# SMC_ISO_Interface_V2_0.net
KiCad netlist of a schematic drawn in EAGLE
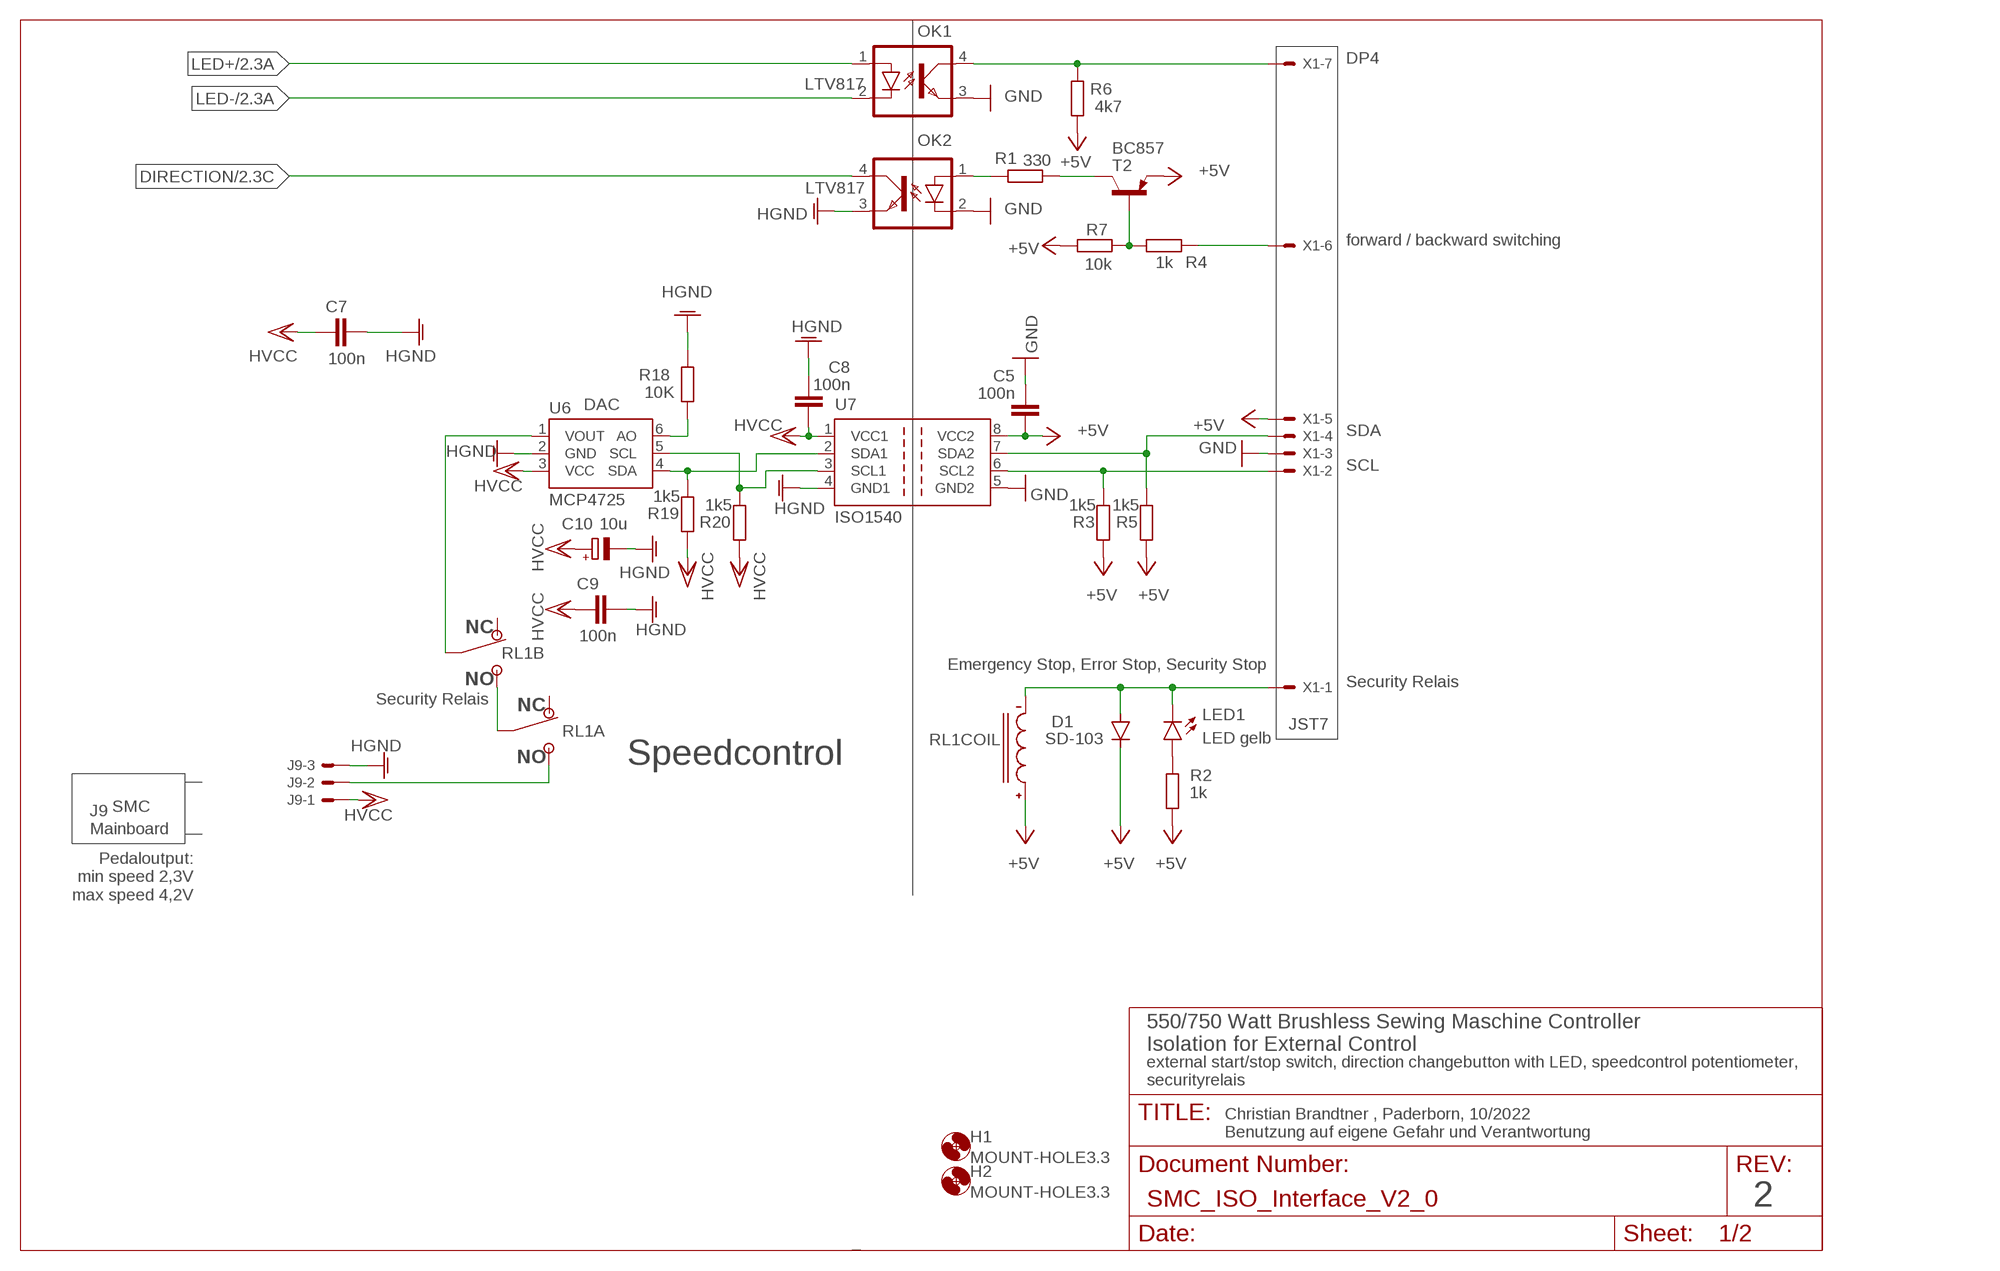
[diagram p0: schematic, sheet 1]
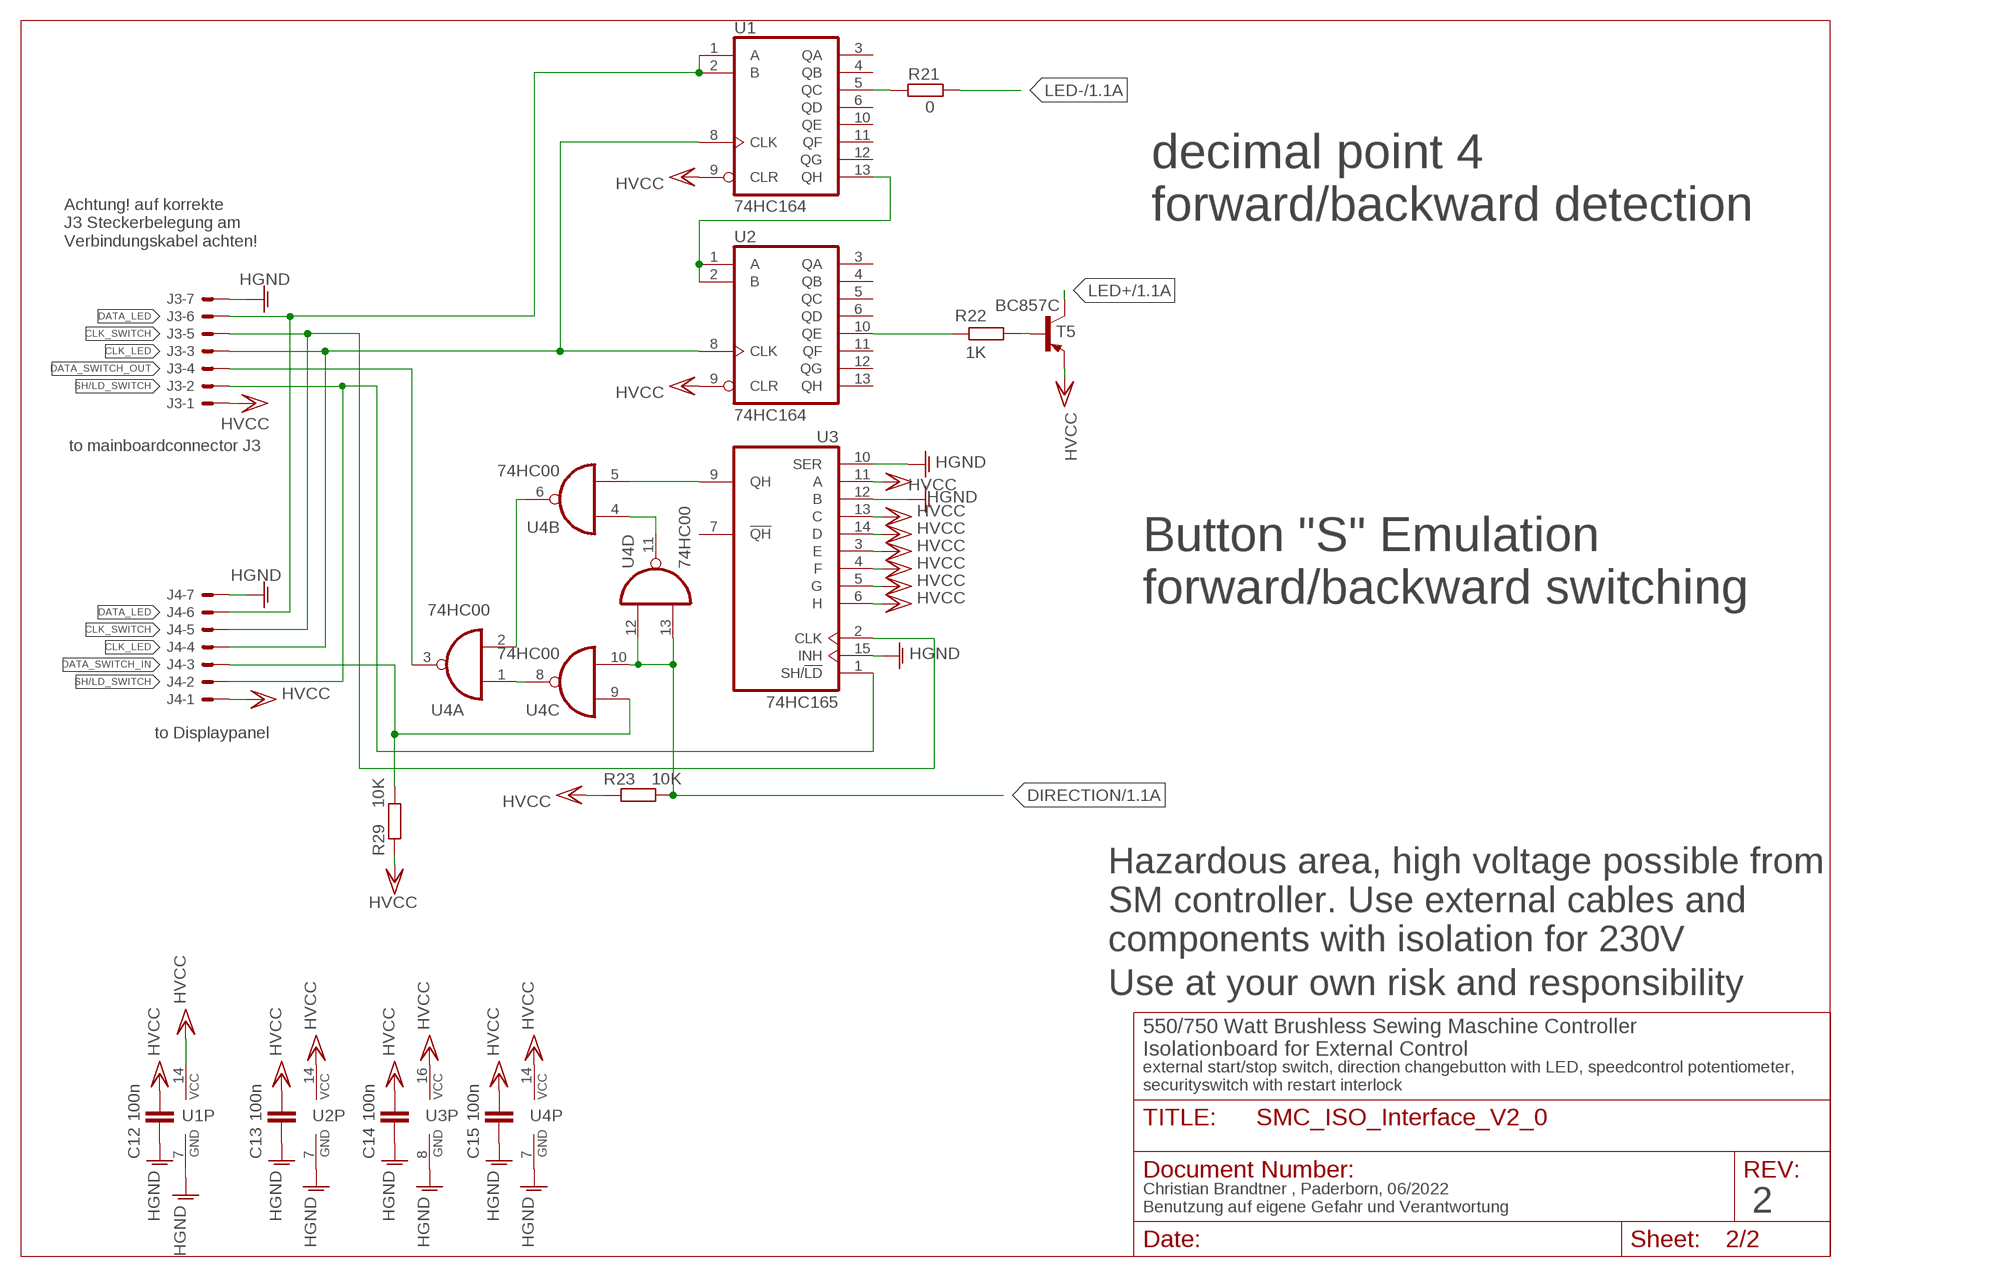
[diagram p1: schematic, sheet 2]

(export (version "E")
  (design (tool "Eeschema 10.0.6"))
  (components
    (comp (ref "C5")
      (value "100n")
      (footprint "eagle-import:C0805")
      (libsource (lib "eagle-import") (part "C-EUC0805"))
    )
    (comp (ref "C7")
      (value "100n")
      (footprint "eagle-import:C0805")
      (libsource (lib "eagle-import") (part "C-EUC0805"))
    )
    (comp (ref "C8")
      (value "100n")
      (footprint "eagle-import:C0805")
      (libsource (lib "eagle-import") (part "C-EUC0805"))
    )
    (comp (ref "C9")
      (value "100n")
      (footprint "eagle-import:C0805")
      (libsource (lib "eagle-import") (part "C-EUC0805"))
    )
    (comp (ref "C10")
      (value "10u")
      (footprint "eagle-import:153CLV-0405")
      (libsource (lib "eagle-import") (part "CPOL-EU153CLV-0405"))
    )
    (comp (ref "D1")
      (value "SD-103")
      (footprint "eagle-import:SOD-123_MINI-SMA")
      (libsource (lib "eagle-import") (part "CGRM400-G1"))
    )
    (comp (ref "H1")
      (value "MOUNT-HOLE3.3")
      (footprint "eagle-import:3,3")
      (libsource (lib "eagle-import") (part "MOUNT-HOLE3.3"))
    )
    (comp (ref "H2")
      (value "MOUNT-HOLE3.3")
      (footprint "eagle-import:3,3")
      (libsource (lib "eagle-import") (part "MOUNT-HOLE3.3"))
    )
    (comp (ref "J9")
      (value "JST-XH-03-PIN-ROUND-PAD")
      (footprint "eagle-import:JST-XH-03-PACKAGE-ROUND-PAD")
      (libsource (lib "eagle-import") (part "JST-XH-03-PIN-ROUND-PAD"))
    )
    (comp (ref "LED1")
      (value "LED gelb")
      (footprint "eagle-import:CHIP-LED0805")
      (libsource (lib "eagle-import") (part "LEDCHIP-LED0805"))
    )
    (comp (ref "OK1")
      (value "LTV817")
      (footprint "eagle-import:SMD4-7")
      (fields (field (name "MF") "VISHAY/TELEFUNKEN") (field (name "MPN") "SFH6186-2"))
      (libsource (lib "eagle-import") (part "SFH618?6-2"))
    )
    (comp (ref "OK2")
      (value "LTV817")
      (footprint "eagle-import:SMD4-7")
      (fields (field (name "MF") "VISHAY/TELEFUNKEN") (field (name "MPN") "SFH6186-2"))
      (libsource (lib "eagle-import") (part "SFH618?6-2"))
    )
    (comp (ref "R1")
      (value "330")
      (footprint "eagle-import:R0805")
      (libsource (lib "eagle-import") (part "R-EU_R0805"))
    )
    (comp (ref "R2")
      (value "1k")
      (footprint "eagle-import:R0805")
      (libsource (lib "eagle-import") (part "R-EU_R0805"))
    )
    (comp (ref "R3")
      (value "1k5")
      (footprint "eagle-import:R0805")
      (libsource (lib "eagle-import") (part "R-EU_R0805"))
    )
    (comp (ref "R4")
      (value "1k")
      (footprint "eagle-import:R0805")
      (libsource (lib "eagle-import") (part "R-EU_R0805"))
    )
    (comp (ref "R5")
      (value "1k5")
      (footprint "eagle-import:R0805")
      (libsource (lib "eagle-import") (part "R-EU_R0805"))
    )
    (comp (ref "R6")
      (value "4k7")
      (footprint "eagle-import:R0805")
      (libsource (lib "eagle-import") (part "R-EU_R0805"))
    )
    (comp (ref "R7")
      (value "10k")
      (footprint "eagle-import:R0805")
      (libsource (lib "eagle-import") (part "R-EU_R0805"))
    )
    (comp (ref "R18")
      (value "10K")
      (footprint "eagle-import:R0805")
      (libsource (lib "eagle-import") (part "R-EU_R0805"))
    )
    (comp (ref "R19")
      (value "1k5")
      (footprint "eagle-import:R0805")
      (libsource (lib "eagle-import") (part "R-EU_R0805"))
    )
    (comp (ref "R20")
      (value "1k5")
      (footprint "eagle-import:R0805")
      (libsource (lib "eagle-import") (part "R-EU_R0805"))
    )
    (comp (ref "RL1")
      (value "G6K-2F-DC5")
      (footprint "eagle-import:F")
      (libsource (lib "eagle-import") (part "G6K-2?F-DC5"))
    )
    (comp (ref "T2")
      (value "BC857")
      (footprint "eagle-import:SOT23-BEC")
      (libsource (lib "eagle-import") (part "BC857SMDA"))
    )
    (comp (ref "U6")
      (value "MCP4725")
      (footprint "eagle-import:SOT23-6")
      (libsource (lib "eagle-import") (part "MCP4725SOT-23"))
    )
    (comp (ref "U7")
      (value "ISO1540")
      (footprint "eagle-import:SO-08")
      (libsource (lib "eagle-import") (part "ISO1540"))
    )
    (comp (ref "X1")
      (value "JST7")
      (footprint "eagle-import:JST-XH-07-PACKAGE-ROUND-PAD")
      (libsource (lib "eagle-import") (part "JST-XH-07-PIN-ROUND-PAD"))
    )
    (comp (ref "C12")
      (value "100n")
      (footprint "eagle-import:C0805")
      (libsource (lib "eagle-import") (part "C-EUC0805"))
    )
    (comp (ref "C13")
      (value "100n")
      (footprint "eagle-import:C0805")
      (libsource (lib "eagle-import") (part "C-EUC0805"))
    )
    (comp (ref "C14")
      (value "100n")
      (footprint "eagle-import:C0805")
      (libsource (lib "eagle-import") (part "C-EUC0805"))
    )
    (comp (ref "C15")
      (value "100n")
      (footprint "eagle-import:C0805")
      (libsource (lib "eagle-import") (part "C-EUC0805"))
    )
    (comp (ref "J3")
      (value "to mainboardconnector J3")
      (footprint "eagle-import:JST-XH-07-PACKAGE-ROUND-PAD")
      (libsource (lib "eagle-import") (part "JST-XH-07-PIN-ROUND-PAD"))
    )
    (comp (ref "J4")
      (value "to Displaypanel")
      (footprint "eagle-import:JST-XH-07-PACKAGE-ROUND-PAD")
      (libsource (lib "eagle-import") (part "JST-XH-07-PIN-ROUND-PAD"))
    )
    (comp (ref "R21")
      (value "0")
      (footprint "eagle-import:R0805")
      (libsource (lib "eagle-import") (part "R-EU_R0805"))
    )
    (comp (ref "R22")
      (value "1K")
      (footprint "eagle-import:R0805")
      (libsource (lib "eagle-import") (part "R-EU_R0805"))
    )
    (comp (ref "R23")
      (value "10K")
      (footprint "eagle-import:R0805")
      (libsource (lib "eagle-import") (part "R-EU_R0805"))
    )
    (comp (ref "R29")
      (value "10K")
      (footprint "eagle-import:R0805")
      (libsource (lib "eagle-import") (part "R-EU_R0805"))
    )
    (comp (ref "T5")
      (value "BC857C")
      (footprint "eagle-import:SOT23-BEC")
      (libsource (lib "eagle-import") (part "-PNP-SOT23-BECBC857C"))
    )
    (comp (ref "U1")
      (value "74HC164")
      (footprint "eagle-import:SO14")
      (libsource (lib "eagle-import") (part "74164DHC"))
    )
    (comp (ref "U2")
      (value "74HC164")
      (footprint "eagle-import:SO14")
      (libsource (lib "eagle-import") (part "74164DHC"))
    )
    (comp (ref "U3")
      (value "74HC165")
      (footprint "eagle-import:SO16")
      (libsource (lib "eagle-import") (part "74165DHC"))
    )
    (comp (ref "U4")
      (value "74HC00")
      (footprint "eagle-import:SO14")
      (libsource (lib "eagle-import") (part "7400DHC"))
    )
  )
  (nets
    (net (code "1") (name "+5V") (class "Default")
      (node (ref "C5") (pin "1") (pinfunction "1_1") (pintype "passive"))
      (node (ref "D1") (pin "C") (pinfunction "C_C") (pintype "passive"))
      (node (ref "R2") (pin "1") (pinfunction "1_1") (pintype "passive"))
      (node (ref "R3") (pin "2") (pinfunction "2_2") (pintype "passive"))
      (node (ref "R5") (pin "2") (pinfunction "2_2") (pintype "passive"))
      (node (ref "R6") (pin "2") (pinfunction "2_2") (pintype "passive"))
      (node (ref "R7") (pin "1") (pinfunction "1_1") (pintype "passive"))
      (node (ref "RL1") (pin "P$1") (pinfunction "C1_P$1") (pintype "bidirectional"))
      (node (ref "T2") (pin "E") (pinfunction "E_E") (pintype "passive"))
      (node (ref "U7") (pin "8") (pinfunction "VCC2_8") (pintype "power_in"))
      (node (ref "X1") (pin "5") (pinfunction "S_5") (pintype "passive"))
    )
    (net (code "2") (name "CLK_LED") (class "Default")
      (node (ref "J3") (pin "3") (pinfunction "S_3") (pintype "passive"))
      (node (ref "J4") (pin "4") (pinfunction "S_4") (pintype "passive"))
      (node (ref "U1") (pin "8") (pinfunction "CLK_8") (pintype "input"))
      (node (ref "U2") (pin "8") (pinfunction "CLK_8") (pintype "input"))
    )
    (net (code "3") (name "CLK_SWITCH") (class "Default")
      (node (ref "J3") (pin "5") (pinfunction "S_5") (pintype "passive"))
      (node (ref "J4") (pin "5") (pinfunction "S_5") (pintype "passive"))
      (node (ref "U3") (pin "2") (pinfunction "CLK_2") (pintype "input"))
    )
    (net (code "4") (name "DATA_LED") (class "Default")
      (node (ref "J3") (pin "6") (pinfunction "S_6") (pintype "passive"))
      (node (ref "J4") (pin "6") (pinfunction "S_6") (pintype "passive"))
      (node (ref "U1") (pin "1") (pinfunction "A_1") (pintype "input"))
      (node (ref "U1") (pin "2") (pinfunction "B_2") (pintype "input"))
    )
    (net (code "5") (name "DATA_SWITCH_IN") (class "Default")
      (node (ref "J4") (pin "3") (pinfunction "S_3") (pintype "passive"))
      (node (ref "R29") (pin "1") (pinfunction "1_1") (pintype "passive"))
      (node (ref "U4") (pin "9") (pinfunction "I0_9") (pintype "input"))
    )
    (net (code "6") (name "DATA_SWITCH_OUT") (class "Default")
      (node (ref "J3") (pin "4") (pinfunction "S_4") (pintype "passive"))
      (node (ref "U4") (pin "3") (pinfunction "O_3") (pintype "output"))
    )
    (net (code "7") (name "DIRECTION") (class "Default")
      (node (ref "OK2") (pin "4") (pinfunction "COL_4") (pintype "passive"))
      (node (ref "R23") (pin "1") (pinfunction "1_1") (pintype "passive"))
      (node (ref "U4") (pin "10") (pinfunction "I1_10") (pintype "input"))
      (node (ref "U4") (pin "12") (pinfunction "I0_12") (pintype "input"))
      (node (ref "U4") (pin "13") (pinfunction "I1_13") (pintype "input"))
    )
    (net (code "8") (name "GND") (class "Default")
      (node (ref "C5") (pin "2") (pinfunction "2_2") (pintype "passive"))
      (node (ref "OK1") (pin "3") (pinfunction "EMIT_3") (pintype "passive"))
      (node (ref "OK2") (pin "2") (pinfunction "C_2") (pintype "passive"))
      (node (ref "U7") (pin "5") (pinfunction "GND2_5") (pintype "power_in"))
      (node (ref "X1") (pin "3") (pinfunction "S_3") (pintype "passive"))
    )
    (net (code "9") (name "HGND") (class "Default")
      (node (ref "C10") (pin "-") (pinfunction "-_-") (pintype "passive"))
      (node (ref "C12") (pin "1") (pinfunction "1_1") (pintype "passive"))
      (node (ref "C13") (pin "1") (pinfunction "1_1") (pintype "passive"))
      (node (ref "C14") (pin "1") (pinfunction "1_1") (pintype "passive"))
      (node (ref "C15") (pin "1") (pinfunction "1_1") (pintype "passive"))
      (node (ref "C7") (pin "1") (pinfunction "1_1") (pintype "passive"))
      (node (ref "C8") (pin "2") (pinfunction "2_2") (pintype "passive"))
      (node (ref "C9") (pin "1") (pinfunction "1_1") (pintype "passive"))
      (node (ref "J3") (pin "7") (pinfunction "S_7") (pintype "passive"))
      (node (ref "J4") (pin "7") (pinfunction "S_7") (pintype "passive"))
      (node (ref "J9") (pin "3") (pinfunction "S_3") (pintype "passive"))
      (node (ref "OK2") (pin "3") (pinfunction "EMIT_3") (pintype "passive"))
      (node (ref "R18") (pin "1") (pinfunction "1_1") (pintype "passive"))
      (node (ref "U1") (pin "7") (pinfunction "GND_7") (pintype "power_in"))
      (node (ref "U2") (pin "7") (pinfunction "GND_7") (pintype "power_in"))
      (node (ref "U3") (pin "10") (pinfunction "SER_10") (pintype "input"))
      (node (ref "U3") (pin "12") (pinfunction "B_12") (pintype "input"))
      (node (ref "U3") (pin "15") (pinfunction "INH_15") (pintype "input"))
      (node (ref "U3") (pin "8") (pinfunction "GND_8") (pintype "power_in"))
      (node (ref "U4") (pin "7") (pinfunction "GND_7") (pintype "power_in"))
      (node (ref "U6") (pin "2") (pinfunction "GND_2") (pintype "bidirectional"))
      (node (ref "U7") (pin "4") (pinfunction "GND1_4") (pintype "power_in"))
    )
    (net (code "10") (name "HVCC") (class "Default")
      (node (ref "C10") (pin "+") (pinfunction "+_+") (pintype "passive"))
      (node (ref "C12") (pin "2") (pinfunction "2_2") (pintype "passive"))
      (node (ref "C13") (pin "2") (pinfunction "2_2") (pintype "passive"))
      (node (ref "C14") (pin "2") (pinfunction "2_2") (pintype "passive"))
      (node (ref "C15") (pin "2") (pinfunction "2_2") (pintype "passive"))
      (node (ref "C7") (pin "2") (pinfunction "2_2") (pintype "passive"))
      (node (ref "C8") (pin "1") (pinfunction "1_1") (pintype "passive"))
      (node (ref "C9") (pin "2") (pinfunction "2_2") (pintype "passive"))
      (node (ref "J3") (pin "1") (pinfunction "S_1") (pintype "passive"))
      (node (ref "J4") (pin "1") (pinfunction "S_1") (pintype "passive"))
      (node (ref "J9") (pin "1") (pinfunction "S_1") (pintype "passive"))
      (node (ref "R19") (pin "2") (pinfunction "2_2") (pintype "passive"))
      (node (ref "R20") (pin "2") (pinfunction "2_2") (pintype "passive"))
      (node (ref "R23") (pin "2") (pinfunction "2_2") (pintype "passive"))
      (node (ref "R29") (pin "2") (pinfunction "2_2") (pintype "passive"))
      (node (ref "T5") (pin "E") (pinfunction "E_E") (pintype "passive"))
      (node (ref "U1") (pin "14") (pinfunction "VCC_14") (pintype "power_in"))
      (node (ref "U1") (pin "9") (pinfunction "CLR_9") (pintype "input"))
      (node (ref "U2") (pin "14") (pinfunction "VCC_14") (pintype "power_in"))
      (node (ref "U2") (pin "9") (pinfunction "CLR_9") (pintype "input"))
      (node (ref "U3") (pin "11") (pinfunction "A_11") (pintype "input"))
      (node (ref "U3") (pin "13") (pinfunction "C_13") (pintype "input"))
      (node (ref "U3") (pin "14") (pinfunction "D_14") (pintype "input"))
      (node (ref "U3") (pin "16") (pinfunction "VCC_16") (pintype "power_in"))
      (node (ref "U3") (pin "3") (pinfunction "E_3") (pintype "input"))
      (node (ref "U3") (pin "4") (pinfunction "F_4") (pintype "input"))
      (node (ref "U3") (pin "5") (pinfunction "G_5") (pintype "input"))
      (node (ref "U3") (pin "6") (pinfunction "H_6") (pintype "input"))
      (node (ref "U4") (pin "14") (pinfunction "VCC_14") (pintype "power_in"))
      (node (ref "U6") (pin "3") (pinfunction "VCC_3") (pintype "bidirectional"))
      (node (ref "U7") (pin "1") (pinfunction "VCC1_1") (pintype "power_in"))
    )
    (net (code "11") (name "LED+") (class "Default")
      (node (ref "OK1") (pin "1") (pinfunction "A_1") (pintype "passive"))
      (node (ref "T5") (pin "C") (pinfunction "C_C") (pintype "passive"))
    )
    (net (code "12") (name "LED-") (class "Default")
      (node (ref "OK1") (pin "2") (pinfunction "C_2") (pintype "passive"))
      (node (ref "R21") (pin "2") (pinfunction "2_2") (pintype "passive"))
    )
    (net (code "13") (name "Net-(J9B-S)") (class "Default")
      (node (ref "J9") (pin "2") (pinfunction "S_2") (pintype "passive"))
      (node (ref "RL1") (pin "P$4") (pinfunction "NO_P$4") (pintype "bidirectional"))
    )
    (net (code "14") (name "Net-(LED1-PadA)") (class "Default")
      (node (ref "LED1") (pin "A") (pinfunction "A_A") (pintype "passive"))
      (node (ref "R2") (pin "2") (pinfunction "2_2") (pintype "passive"))
    )
    (net (code "15") (name "Net-(OK1-COL)") (class "Default")
      (node (ref "OK1") (pin "4") (pinfunction "COL_4") (pintype "passive"))
      (node (ref "R6") (pin "1") (pinfunction "1_1") (pintype "passive"))
      (node (ref "X1") (pin "7") (pinfunction "S_7") (pintype "passive"))
    )
    (net (code "16") (name "Net-(OK2-A)") (class "Default")
      (node (ref "OK2") (pin "1") (pinfunction "A_1") (pintype "passive"))
      (node (ref "R1") (pin "2") (pinfunction "2_2") (pintype "passive"))
    )
    (net (code "17") (name "Net-(R1-Pad1)") (class "Default")
      (node (ref "R1") (pin "1") (pinfunction "1_1") (pintype "passive"))
      (node (ref "T2") (pin "C") (pinfunction "C_C") (pintype "passive"))
    )
    (net (code "18") (name "Net-(R4-Pad1)") (class "Default")
      (node (ref "R4") (pin "1") (pinfunction "1_1") (pintype "passive"))
      (node (ref "R7") (pin "2") (pinfunction "2_2") (pintype "passive"))
      (node (ref "T2") (pin "B") (pinfunction "B_B") (pintype "passive"))
    )
    (net (code "19") (name "Net-(R22-Pad1)") (class "Default")
      (node (ref "R22") (pin "1") (pinfunction "1_1") (pintype "passive"))
      (node (ref "T5") (pin "B") (pinfunction "B_B") (pintype "passive"))
    )
    (net (code "20") (name "Net-(RL1A-C)") (class "Default")
      (node (ref "RL1") (pin "P$3") (pinfunction "C_P$3") (pintype "bidirectional"))
      (node (ref "RL1") (pin "P$5") (pinfunction "NO_P$5") (pintype "bidirectional"))
    )
    (net (code "21") (name "Net-(RL1B-C)") (class "Default")
      (node (ref "RL1") (pin "P$6") (pinfunction "C_P$6") (pintype "bidirectional"))
      (node (ref "U6") (pin "1") (pinfunction "VOUT_1") (pintype "bidirectional"))
    )
    (net (code "22") (name "Net-(RL1C-C2)") (class "Default")
      (node (ref "D1") (pin "A") (pinfunction "A_A") (pintype "passive"))
      (node (ref "LED1") (pin "C") (pinfunction "C_C") (pintype "passive"))
      (node (ref "RL1") (pin "P$8") (pinfunction "C2_P$8") (pintype "bidirectional"))
      (node (ref "X1") (pin "1") (pinfunction "S_1") (pintype "passive"))
    )
    (net (code "23") (name "Net-(U1A-QC)") (class "Default")
      (node (ref "R21") (pin "1") (pinfunction "1_1") (pintype "passive"))
      (node (ref "U1") (pin "5") (pinfunction "QC_5") (pintype "output"))
    )
    (net (code "24") (name "Net-(U1A-QH)") (class "Default")
      (node (ref "U1") (pin "13") (pinfunction "QH_13") (pintype "output"))
      (node (ref "U2") (pin "1") (pinfunction "A_1") (pintype "input"))
      (node (ref "U2") (pin "2") (pinfunction "B_2") (pintype "input"))
    )
    (net (code "25") (name "Net-(U2A-QE)") (class "Default")
      (node (ref "R22") (pin "2") (pinfunction "2_2") (pintype "passive"))
      (node (ref "U2") (pin "10") (pinfunction "QE_10") (pintype "output"))
    )
    (net (code "26") (name "Net-(U3A-QH)") (class "Default")
      (node (ref "U3") (pin "9") (pinfunction "QH_9") (pintype "output"))
      (node (ref "U4") (pin "5") (pinfunction "I1_5") (pintype "input"))
    )
    (net (code "27") (name "Net-(U4A-I0)") (class "Default")
      (node (ref "U4") (pin "1") (pinfunction "I0_1") (pintype "input"))
      (node (ref "U4") (pin "8") (pinfunction "O_8") (pintype "output"))
    )
    (net (code "28") (name "Net-(U4A-I1)") (class "Default")
      (node (ref "U4") (pin "2") (pinfunction "I1_2") (pintype "input"))
      (node (ref "U4") (pin "6") (pinfunction "O_6") (pintype "output"))
    )
    (net (code "29") (name "Net-(U4B-I0)") (class "Default")
      (node (ref "U4") (pin "11") (pinfunction "O_11") (pintype "output"))
      (node (ref "U4") (pin "4") (pinfunction "I0_4") (pintype "input"))
    )
    (net (code "30") (name "Net-(U6-AO)") (class "Default")
      (node (ref "R18") (pin "2") (pinfunction "2_2") (pintype "passive"))
      (node (ref "U6") (pin "6") (pinfunction "AO_6") (pintype "bidirectional"))
    )
    (net (code "31") (name "Net-(U6-SCL)") (class "Default")
      (node (ref "R20") (pin "1") (pinfunction "1_1") (pintype "passive"))
      (node (ref "U6") (pin "5") (pinfunction "SCL_5") (pintype "bidirectional"))
      (node (ref "U7") (pin "3") (pinfunction "SCL1_3") (pintype "input"))
    )
    (net (code "32") (name "Net-(U6-SDA)") (class "Default")
      (node (ref "R19") (pin "1") (pinfunction "1_1") (pintype "passive"))
      (node (ref "U6") (pin "4") (pinfunction "SDA_4") (pintype "bidirectional"))
      (node (ref "U7") (pin "2") (pinfunction "SDA1_2") (pintype "input"))
    )
    (net (code "33") (name "Net-(U7-SCL2)") (class "Default")
      (node (ref "R3") (pin "1") (pinfunction "1_1") (pintype "passive"))
      (node (ref "U7") (pin "6") (pinfunction "SCL2_6") (pintype "output"))
      (node (ref "X1") (pin "2") (pinfunction "S_2") (pintype "passive"))
    )
    (net (code "34") (name "Net-(U7-SDA2)") (class "Default")
      (node (ref "R5") (pin "1") (pinfunction "1_1") (pintype "passive"))
      (node (ref "U7") (pin "7") (pinfunction "SDA2_7") (pintype "output"))
      (node (ref "X1") (pin "4") (pinfunction "S_4") (pintype "passive"))
    )
    (net (code "35") (name "Net-(X1F-S)") (class "Default")
      (node (ref "R4") (pin "2") (pinfunction "2_2") (pintype "passive"))
      (node (ref "X1") (pin "6") (pinfunction "S_6") (pintype "passive"))
    )
    (net (code "36") (name "SH{slash}LD_SWITCH") (class "Default")
      (node (ref "J3") (pin "2") (pinfunction "S_2") (pintype "passive"))
      (node (ref "J4") (pin "2") (pinfunction "S_2") (pintype "passive"))
      (node (ref "U3") (pin "1") (pinfunction "SH/~{LD}_1") (pintype "input"))
    )
    (net (code "37") (name "unconnected-(RL1A-NC-PadP$2)") (class "Default")
      (node (ref "RL1") (pin "P$2") (pinfunction "NC_P$2") (pintype "bidirectional"))
    )
    (net (code "38") (name "unconnected-(RL1B-NC-PadP$7)") (class "Default")
      (node (ref "RL1") (pin "P$7") (pinfunction "NC_P$7") (pintype "bidirectional"))
    )
    (net (code "39") (name "unconnected-(U1A-QA-Pad3)") (class "Default")
      (node (ref "U1") (pin "3") (pinfunction "QA_3") (pintype "output"))
    )
    (net (code "40") (name "unconnected-(U1A-QB-Pad4)") (class "Default")
      (node (ref "U1") (pin "4") (pinfunction "QB_4") (pintype "output"))
    )
    (net (code "41") (name "unconnected-(U1A-QD-Pad6)") (class "Default")
      (node (ref "U1") (pin "6") (pinfunction "QD_6") (pintype "output"))
    )
    (net (code "42") (name "unconnected-(U1A-QE-Pad10)") (class "Default")
      (node (ref "U1") (pin "10") (pinfunction "QE_10") (pintype "output"))
    )
    (net (code "43") (name "unconnected-(U1A-QF-Pad11)") (class "Default")
      (node (ref "U1") (pin "11") (pinfunction "QF_11") (pintype "output"))
    )
    (net (code "44") (name "unconnected-(U1A-QG-Pad12)") (class "Default")
      (node (ref "U1") (pin "12") (pinfunction "QG_12") (pintype "output"))
    )
    (net (code "45") (name "unconnected-(U2A-QA-Pad3)") (class "Default")
      (node (ref "U2") (pin "3") (pinfunction "QA_3") (pintype "output"))
    )
    (net (code "46") (name "unconnected-(U2A-QB-Pad4)") (class "Default")
      (node (ref "U2") (pin "4") (pinfunction "QB_4") (pintype "output"))
    )
    (net (code "47") (name "unconnected-(U2A-QC-Pad5)") (class "Default")
      (node (ref "U2") (pin "5") (pinfunction "QC_5") (pintype "output"))
    )
    (net (code "48") (name "unconnected-(U2A-QD-Pad6)") (class "Default")
      (node (ref "U2") (pin "6") (pinfunction "QD_6") (pintype "output"))
    )
    (net (code "49") (name "unconnected-(U2A-QF-Pad11)") (class "Default")
      (node (ref "U2") (pin "11") (pinfunction "QF_11") (pintype "output"))
    )
    (net (code "50") (name "unconnected-(U2A-QG-Pad12)") (class "Default")
      (node (ref "U2") (pin "12") (pinfunction "QG_12") (pintype "output"))
    )
    (net (code "51") (name "unconnected-(U2A-QH-Pad13)") (class "Default")
      (node (ref "U2") (pin "13") (pinfunction "QH_13") (pintype "output"))
    )
    (net (code "52") (name "unconnected-(U3A-~{QH}-Pad7)") (class "Default")
      (node (ref "U3") (pin "7") (pinfunction "~{QH}_7") (pintype "output"))
    )
  )
)
